# Power_Management.net
KiCad netlist of a schematic drawn in Altium Designer
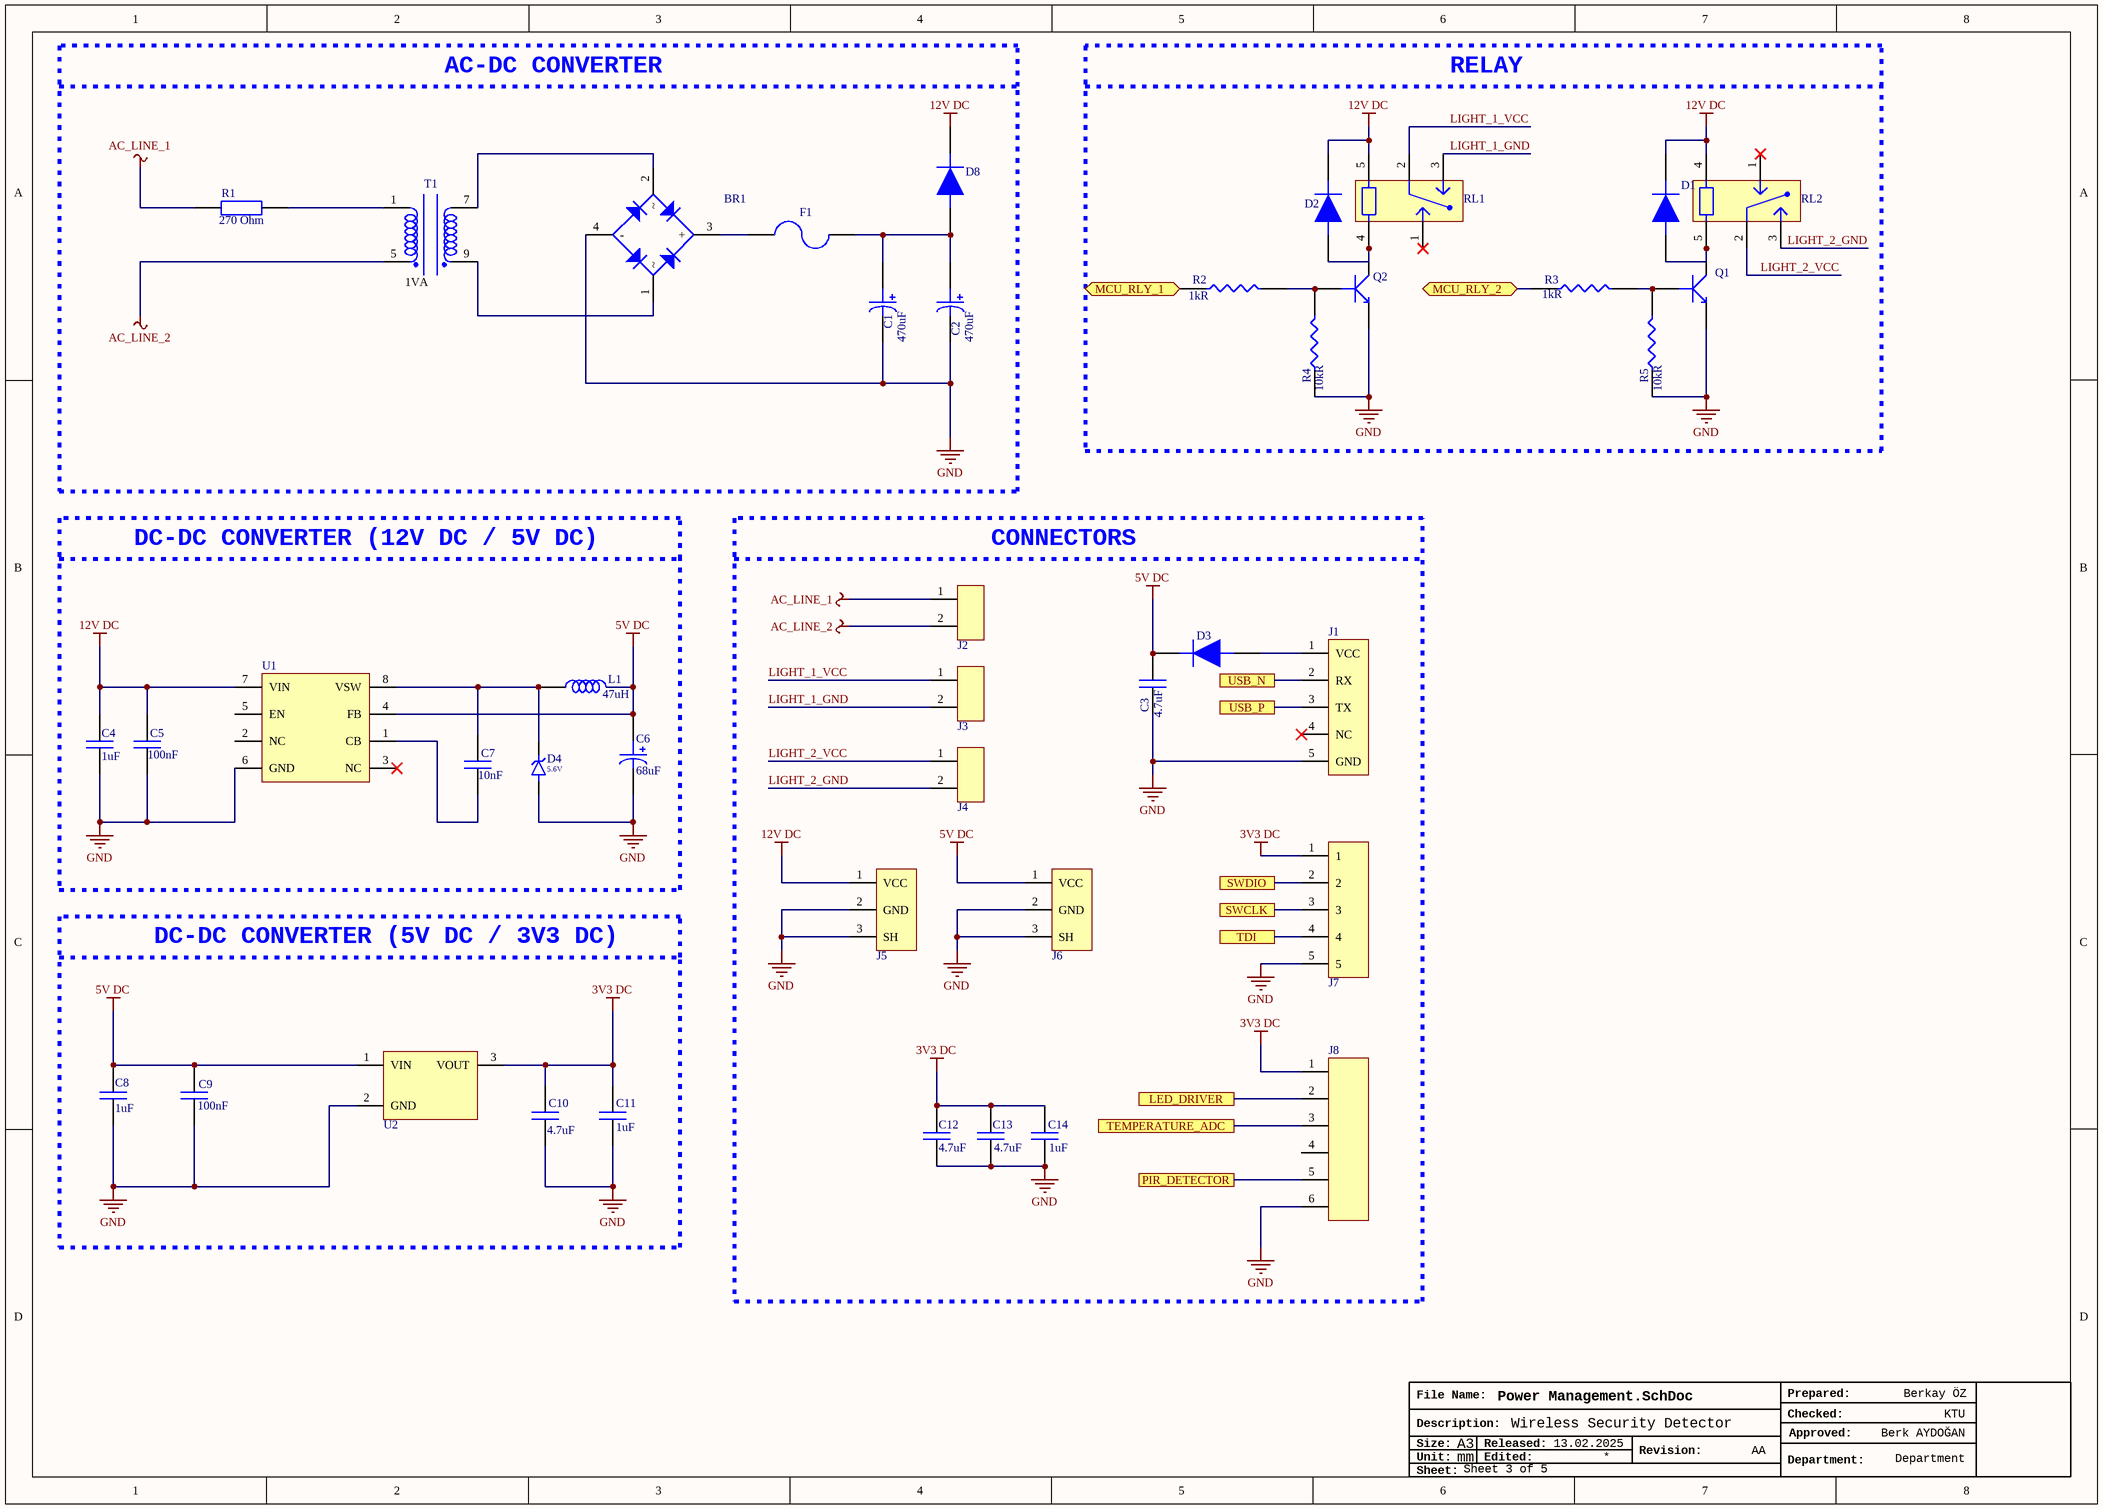
[diagram p0: Power Management.SchDoc]

(export (version "E")
  (design (tool "Eeschema 10.0.6"))
  (components
    (comp (ref "BR1")
      (value "DB105STR")
      (footprint "DB105STR")
      (description "Bridge Rect 1PHASE 600V 1A Db-s")
      (fields
        (field (name "MANUFACTURER") "Sangdest Microelectronics")
        (field (name "MANUFACTURER PART NUMBER") "DB105S")
        (field (name "DESIGNED BY") "berkay")
      )
      (libsource (lib "FirstProject_Library") (part "DB105STR"))
    )
    (comp (ref "C1")
      (value "ESH477M050AH4AA")
      (footprint "CAP_RADIAL_D10_P5")
      (description "Electrolytic capacitor, 470 µF, 50 V (DC), ±20 %, radial, pitch 5 mm, Ø 13 mm")
      (fields
        (field (name "MANUFACTURER") "KEMET")
        (field (name "CAPACITANCE") "470uF")
        (field (name "DESIGNED BY") "berkay")
      )
      (libsource (lib "FirstProject_Library") (part "CAP ALU ELEC 470uF 50V"))
    )
    (comp (ref "C2")
      (value "ESH477M050AH4AA")
      (footprint "CAP_RADIAL_D10_P5")
      (description "Electrolytic capacitor, 470 µF, 50 V (DC), ±20 %, radial, pitch 5 mm, Ø 13 mm")
      (fields
        (field (name "MANUFACTURER") "KEMET")
        (field (name "CAPACITANCE") "470uF")
        (field (name "DESIGNED BY") "berkay")
      )
      (libsource (lib "FirstProject_Library") (part "CAP ALU ELEC 470uF 50V"))
    )
    (comp (ref "C3")
      (value "CL21A475KAQNNNE")
      (footprint "CAP_0805")
      (description "Ceramic Capacitor, 4.7 uF, 25 V, ± 10%, X5R, 0805 [2012 Metric]")
      (fields
        (field (name "MANUFACTURER") "Samsung")
        (field (name "TOLERANCE") "10%")
        (field (name "CAPACITANCE") "4.7uF")
        (field (name "DESIGNED BY") "berkay")
      )
      (libsource (lib "FirstProject_Library") (part "CAP CER 4.7uF 0805"))
    )
    (comp (ref "C4")
      (value "CL21B105KBFNNNE")
      (footprint "CAP_0805")
      (description "Ceramic Capacitor, 1 uF, 50 V, ï¿½ 10%, X7R, 0805 [2012 Metric]")
      (fields
        (field (name "MANUFACTURER") "Samsung")
        (field (name "TOLERANCE") "10%")
        (field (name "CAPACITANCE") "1uF")
        (field (name "DESIGNED BY") "berkay")
      )
      (libsource (lib "FirstProject_Library") (part "CAP CER 1uF 0805"))
    )
    (comp (ref "C5")
      (value "C0603C104K4RACTU")
      (footprint "CAP_0603")
      (description "Ceramic Capacitor, 0.1 uF, 16 V, ï¿½ 10%, X7R, 0603 [1608 Metric]")
      (fields
        (field (name "MANUFACTURER") "KEMET")
        (field (name "TOLERANCE") "10%")
        (field (name "CAPACITANCE") "100nF")
        (field (name "DESIGNED BY") "berkay")
      )
      (libsource (lib "FirstProject_Library") (part "CAP CER 100nF 0603"))
    )
    (comp (ref "C6")
      (value "EEV686M035A9HAA")
      (footprint "CAP_EEVSERIES")
      (description "Cap Aluminum Lytic 68uF 35V 20%( 6.3 X 7.7mm) SMD 0.34 Ohm 280mA 2000h 105C T/R")
      (fields
        (field (name "MANUFACTURER") "KEMET")
        (field (name "CAPACITANCE") "68uF")
        (field (name "DESIGNED BY") "berkay")
      )
      (libsource (lib "FirstProject_Library") (part "CAP ALU 68uF"))
    )
    (comp (ref "C7")
      (value "0603B103K160CT")
      (footprint "CAP_0603")
      (description "Ceramic Capacitor, 10 nF, ± 10%, 0603")
      (fields
        (field (name "MANUFACTURER") "Walsin Technologies")
        (field (name "CAPACITANCE") "10nF")
        (field (name "DESIGNED BY") "berkay")
      )
      (libsource (lib "FirstProject_Library") (part "CAP CER 10nF 0603"))
    )
    (comp (ref "C8")
      (value "CL21B105KBFNNNE")
      (footprint "CAP_0805")
      (description "Ceramic Capacitor, 1 uF, 50 V, ï¿½ 10%, X7R, 0805 [2012 Metric]")
      (fields
        (field (name "MANUFACTURER") "Samsung")
        (field (name "TOLERANCE") "10%")
        (field (name "CAPACITANCE") "1uF")
        (field (name "DESIGNED BY") "berkay")
      )
      (libsource (lib "FirstProject_Library") (part "CAP CER 1uF 0805"))
    )
    (comp (ref "C9")
      (value "C0603C104K4RACTU")
      (footprint "CAP_0603")
      (description "Ceramic Capacitor, 0.1 uF, 16 V, ï¿½ 10%, X7R, 0603 [1608 Metric]")
      (fields
        (field (name "MANUFACTURER") "KEMET")
        (field (name "TOLERANCE") "10%")
        (field (name "CAPACITANCE") "100nF")
        (field (name "DESIGNED BY") "berkay")
      )
      (libsource (lib "FirstProject_Library") (part "CAP CER 100nF 0603"))
    )
    (comp (ref "C10")
      (value "CL21A475KAQNNNE")
      (footprint "CAP_0805")
      (description "Ceramic Capacitor, 4.7 uF, 25 V, ± 10%, X5R, 0805 [2012 Metric]")
      (fields
        (field (name "MANUFACTURER") "Samsung")
        (field (name "TOLERANCE") "10%")
        (field (name "CAPACITANCE") "4.7uF")
        (field (name "DESIGNED BY") "berkay")
      )
      (libsource (lib "FirstProject_Library") (part "CAP CER 4.7uF 0805"))
    )
    (comp (ref "C11")
      (value "CL21B105KBFNNNE")
      (footprint "CAP_0805")
      (description "Ceramic Capacitor, 1 uF, 50 V, ï¿½ 10%, X7R, 0805 [2012 Metric]")
      (fields
        (field (name "MANUFACTURER") "Samsung")
        (field (name "TOLERANCE") "10%")
        (field (name "CAPACITANCE") "1uF")
        (field (name "DESIGNED BY") "berkay")
      )
      (libsource (lib "FirstProject_Library") (part "CAP CER 1uF 0805"))
    )
    (comp (ref "C12")
      (value "CL21A475KAQNNNE")
      (footprint "CAP_0805")
      (description "Ceramic Capacitor, 4.7 uF, 25 V, ± 10%, X5R, 0805 [2012 Metric]")
      (fields
        (field (name "MANUFACTURER") "Samsung")
        (field (name "TOLERANCE") "10%")
        (field (name "CAPACITANCE") "4.7uF")
        (field (name "DESIGNED BY") "berkay")
      )
      (libsource (lib "FirstProject_Library") (part "CAP CER 4.7uF 0805"))
    )
    (comp (ref "C13")
      (value "CL21A475KAQNNNE")
      (footprint "CAP_0805")
      (description "Ceramic Capacitor, 4.7 uF, 25 V, ± 10%, X5R, 0805 [2012 Metric]")
      (fields
        (field (name "MANUFACTURER") "Samsung")
        (field (name "TOLERANCE") "10%")
        (field (name "CAPACITANCE") "4.7uF")
        (field (name "DESIGNED BY") "berkay")
      )
      (libsource (lib "FirstProject_Library") (part "CAP CER 4.7uF 0805"))
    )
    (comp (ref "C14")
      (value "CL21B105KBFNNNE")
      (footprint "CAP_0805")
      (description "Ceramic Capacitor, 1 uF, 50 V, ï¿½ 10%, X7R, 0805 [2012 Metric]")
      (fields
        (field (name "MANUFACTURER") "Samsung")
        (field (name "TOLERANCE") "10%")
        (field (name "CAPACITANCE") "1uF")
        (field (name "DESIGNED BY") "berkay")
      )
      (libsource (lib "FirstProject_Library") (part "CAP CER 1uF 0805"))
    )
    (comp (ref "D1")
      (value "1N4148WS")
      (footprint "SOD323F")
      (description "Diode Ultra Fast Recovery Rectifier 75V 0.15A 2-Pin SOD-323F T/R")
      (fields
        (field (name "MANUFACTURER") "ON Semiconductor / Fairchild")
        (field (name "DESIGNED BY") "berkay")
      )
      (libsource (lib "FirstProject_Library") (part "1N4148WS"))
    )
    (comp (ref "D2")
      (value "1N4148WS")
      (footprint "SOD323F")
      (description "Diode Ultra Fast Recovery Rectifier 75V 0.15A 2-Pin SOD-323F T/R")
      (fields
        (field (name "MANUFACTURER") "ON Semiconductor / Fairchild")
        (field (name "DESIGNED BY") "berkay")
      )
      (libsource (lib "FirstProject_Library") (part "1N4148WS"))
    )
    (comp (ref "D3")
      (value "1N4148WS")
      (footprint "SOD323F")
      (description "Diode Ultra Fast Recovery Rectifier 75V 0.15A 2-Pin SOD-323F T/R")
      (fields
        (field (name "MANUFACTURER") "ON Semiconductor / Fairchild")
        (field (name "DESIGNED BY") "berkay")
      )
      (libsource (lib "FirstProject_Library") (part "1N4148WS"))
    )
    (comp (ref "D4")
      (value "1SMB5919BT3G")
      (footprint "SMB")
      (description "Zener Diode 5.6 V 3 W ±5% Surface Mount SMB")
      (fields
        (field (name "MANUFACTURER") "ON Semiconductor")
        (field (name "VOLTAGE RATING (DC)") "5.6V")
        (field (name "DESIGNED BY") "berkay")
      )
      (libsource (lib "FirstProject_Library") (part "1SMB5919BT3G"))
    )
    (comp (ref "D8")
      (value "1N4148WS")
      (footprint "SOD323F")
      (description "Diode Ultra Fast Recovery Rectifier 75V 0.15A 2-Pin SOD-323F T/R")
      (fields
        (field (name "MANUFACTURER") "ON Semiconductor / Fairchild")
        (field (name "DESIGNED BY") "berkay")
      )
      (libsource (lib "FirstProject_Library") (part "1N4148WS"))
    )
    (comp (ref "F1")
      (value "3413.0216.22")
      (footprint "3413.0216.22")
      (description "Fuse Chip Fast Acting 1A 32V SMD Solder Pad 1206 Glass T/R VDE/cULus")
      (fields (field (name "MANUFACTURER") "Schurter") (field (name "DESIGNED BY") "berkay"))
      (libsource (lib "FirstProject_Library") (part "FUSE 3413.0216.22"))
    )
    (comp (ref "J1")
      (value "10118192-0001LF")
      (footprint "MICRO_B_USB")
      (description "CONN USB MICRO B RECPT SMT R/A\r\n(Designator'e USB?'de denebilirdi)")
      (fields (field (name "MANUFACTURER") "Amphenol ICC / FCI") (field (name "DESIGNED BY") "berkay"))
      (libsource (lib "FirstProject_Library") (part "Micro B USB Connector"))
    )
    (comp (ref "J2")
      (value "TBP01R1-508-02BE")
      (footprint "TBP01R1-508")
      (description "2~24 Poles, Pluggable, Receptacle, Horizontal, 5.08 Pitch, Terminal Block Connector")
      (fields (field (name "MANUFACTURER") "CUI Devices") (field (name "DESIGNED BY") "berkay"))
      (libsource (lib "FirstProject_Library") (part "TBP01R1-508-02BE"))
    )
    (comp (ref "J3")
      (value "TBP01R1-508-02BE")
      (footprint "TBP01R1-508")
      (description "2~24 Poles, Pluggable, Receptacle, Horizontal, 5.08 Pitch, Terminal Block Connector")
      (fields (field (name "MANUFACTURER") "CUI Devices") (field (name "DESIGNED BY") "berkay"))
      (libsource (lib "FirstProject_Library") (part "TBP01R1-508-02BE"))
    )
    (comp (ref "J4")
      (value "TBP01R1-508-02BE")
      (footprint "TBP01R1-508")
      (description "2~24 Poles, Pluggable, Receptacle, Horizontal, 5.08 Pitch, Terminal Block Connector")
      (fields (field (name "MANUFACTURER") "CUI Devices") (field (name "DESIGNED BY") "berkay"))
      (libsource (lib "FirstProject_Library") (part "TBP01R1-508-02BE"))
    )
    (comp (ref "J5")
      (value "PJ-037AH-SMT-TR")
      (footprint "JACK")
      (description "2.0 x 6.3 mm, 5.0 A, Horizontal, Surface Mount (SMT), Dc Power Jack Connector")
      (fields (field (name "MANUFACTURER") "CUI") (field (name "DESIGNED BY") "berkay"))
      (libsource (lib "FirstProject_Library") (part "PJ-037AH-SMT-TR"))
    )
    (comp (ref "J6")
      (value "PJ-037AH-SMT-TR")
      (footprint "JACK")
      (description "2.0 x 6.3 mm, 5.0 A, Horizontal, Surface Mount (SMT), Dc Power Jack Connector")
      (fields (field (name "MANUFACTURER") "CUI") (field (name "DESIGNED BY") "berkay"))
      (libsource (lib "FirstProject_Library") (part "PJ-037AH-SMT-TR"))
    )
    (comp (ref "J7")
      (value "SMH-105-02-L-S")
      (footprint "PIN_HEADER_1X5_RA")
      (description "PCB Receptacle, Board-to-Board, 2.54 mm, 1 Rows, 5 Contacts, Surface Mount, SMH")
      (fields (field (name "MANUFACTURER") "Samtec") (field (name "DESIGNED BY") "berkay"))
      (libsource (lib "FirstProject_Library") (part "SMH-105-02-L-S"))
    )
    (comp (ref "J8")
      (value "64800611622")
      (footprint "64800611622")
      (description "WR-WTB Wire-to-Board Connectors 1.50 mm")
      (fields (field (name "MANUFACTURER") "Wurth Electronics"))
      (libsource (lib "FirstProject_Library") (part "64800611622_conn_6pin"))
    )
    (comp (ref "L1")
      (value "78438335470")
      (footprint "IND_1212")
      (description "Power Inductor, Aec-Q200, 47Uh, 0.39A Rohs Compliant: Yes ¦Wurth Elektronik 78438335470")
      (fields
        (field (name "MANUFACTURER") "Wurth Electronics")
        (field (name "TOLERANCE") "30%")
        (field (name "INDUCTANCE") "47uH")
        (field (name "DESIGNED BY") "berkay")
      )
      (libsource (lib "FirstProject_Library") (part "IND 47uH"))
    )
    (comp (ref "Q1")
      (value "MMBT3904-7-F")
      (footprint "SOT23F")
      (description "Transistor General Purpose BJT NPN 40 Volt 0.2A Automotive 3-Pin SOT-23")
      (fields (field (name "MANUFACTURER") "Diodes Zetex") (field (name "DESIGNED BY") "berkay"))
      (libsource (lib "FirstProject_Library") (part "MMBT3904-7-F"))
    )
    (comp (ref "Q2")
      (value "MMBT3904-7-F")
      (footprint "SOT23F")
      (description "Transistor General Purpose BJT NPN 40 Volt 0.2A Automotive 3-Pin SOT-23")
      (fields (field (name "MANUFACTURER") "Diodes Zetex") (field (name "DESIGNED BY") "berkay"))
      (libsource (lib "FirstProject_Library") (part "MMBT3904-7-F"))
    )
    (comp (ref "R1")
      (value "5WD27")
      (footprint "RES_AXIAL_W")
      (description "270 OHM RESISTOR")
      (fields
        (field (name "TOLERANCE") "5%")
        (field (name "RESISTANCE VALUE") "270 Ohm")
        (field (name "DESIGNED BY") "berkay")
      )
      (libsource (lib "FirstProject_Library") (part "5WD27"))
    )
    (comp (ref "R2")
      (value "RC0603FR-071KL")
      (footprint "RES_0603")
      (description "SMD Chip Resistor, 1 kOhm, ï¿½ 1%, 100 mW, 0603 [1608 Metric], Thick Film, General Purpose")
      (fields
        (field (name "MANUFACTURER") "Yageo")
        (field (name "TOLERANCE") "1%")
        (field (name "RESISTANCE") "1kR")
        (field (name "DESIGNED BY") "berkay")
      )
      (libsource (lib "FirstProject_Library") (part "RES 1K OHM 0603"))
    )
    (comp (ref "R3")
      (value "RC0603FR-071KL")
      (footprint "RES_0603")
      (description "SMD Chip Resistor, 1 kOhm, ï¿½ 1%, 100 mW, 0603 [1608 Metric], Thick Film, General Purpose")
      (fields
        (field (name "MANUFACTURER") "Yageo")
        (field (name "TOLERANCE") "1%")
        (field (name "RESISTANCE") "1kR")
        (field (name "DESIGNED BY") "berkay")
      )
      (libsource (lib "FirstProject_Library") (part "RES 1K OHM 0603"))
    )
    (comp (ref "R4")
      (value "RC0603FR-0710KL")
      (footprint "RES_0603")
      (description "SMD Chip Resistor, 10 kOhm, ï¿½ 1%, 100 mW, 0603 [1608 Metric], Thick Film, General Purpose")
      (fields
        (field (name "MANUFACTURER") "Yageo")
        (field (name "TOLERANCE") "1%")
        (field (name "RESISTANCE") "10kR")
        (field (name "DESIGNED BY") "berkay")
      )
      (libsource (lib "FirstProject_Library") (part "RES 10K OHM 0603"))
    )
    (comp (ref "R5")
      (value "RC0603FR-0710KL")
      (footprint "RES_0603")
      (description "SMD Chip Resistor, 10 kOhm, ï¿½ 1%, 100 mW, 0603 [1608 Metric], Thick Film, General Purpose")
      (fields
        (field (name "MANUFACTURER") "Yageo")
        (field (name "TOLERANCE") "1%")
        (field (name "RESISTANCE") "10kR")
        (field (name "DESIGNED BY") "berkay")
      )
      (libsource (lib "FirstProject_Library") (part "RES 10K OHM 0603"))
    )
    (comp (ref "RL1")
      (value "ALQ112")
      (footprint "ALQ112")
      (description "Electromechanical Relay 12VDC 360Ohm 10(NO)/3(NC)A SPDT (( 20mm 10mm 16mm)) THT Power Relay")
      (fields (field (name "MANUFACTURER") "Panasonic") (field (name "DESIGNED BY") "berkay"))
      (libsource (lib "FirstProject_Library") (part "ALQ112"))
    )
    (comp (ref "RL2")
      (value "ALQ112")
      (footprint "ALQ112")
      (description "Electromechanical Relay 12VDC 360Ohm 10(NO)/3(NC)A SPDT (( 20mm 10mm 16mm)) THT Power Relay")
      (fields (field (name "MANUFACTURER") "Panasonic") (field (name "DESIGNED BY") "berkay"))
      (libsource (lib "") (part "ALQ112_1"))
    )
    (comp (ref "T1")
      (value "BV302S12010-ZU")
      (footprint "BV302S")
      (description "230-12 Transformer 1VA")
      (fields
        (field (name "MANUFACTURER") "Zettler Magnetics")
        (field (name "RATED POWER") "1VA")
        (field (name "DESIGNED BY") "berkay")
      )
      (libsource (lib "FirstProject_Library") (part "BV302S12010-ZU"))
    )
    (comp (ref "U1")
      (value "LM2675MX-12/NOPB")
      (footprint "SOIC 8")
      (description "Buck Switching Regulator IC Positive Fixed 12V 1 Output 1A 8-SOIC (0.154\", 3.90mm Width)")
      (fields (field (name "MANUFACTURER") "TI National Semiconductor") (field (name "DESIGNED BY") "berkay"))
      (libsource (lib "FirstProject_Library") (part "LM2675MX-12/NOPB"))
    )
    (comp (ref "U2")
      (value "AP7361-33E-13")
      (footprint "SOT223")
      (description "AP7361 Series 3.3 V 1 A Low SMT Dropout Fixed-Mode Regulator - SOT-223")
      (fields (field (name "MANUFACTURER") "Diodes") (field (name "DESIGNED BY") "berkay"))
      (libsource (lib "FirstProject_Library") (part "AP7361-33E-13"))
    )
  )
  (nets
    (net (code "1") (name "/LED_DRIVER") (class "Default")
      (node (ref "J8") (pin "2") (pinfunction "2_2") (pintype "passive"))
    )
    (net (code "2") (name "/LIGHT_1_GND") (class "Default")
      (node (ref "J3") (pin "2") (pinfunction "2_2") (pintype "passive"))
      (node (ref "RL1") (pin "3") (pinfunction "3_3") (pintype "passive"))
    )
    (net (code "3") (name "/LIGHT_1_VCC") (class "Default")
      (node (ref "J3") (pin "1") (pinfunction "1_1") (pintype "passive"))
      (node (ref "RL1") (pin "2") (pinfunction "2_2") (pintype "passive"))
    )
    (net (code "4") (name "/LIGHT_2_GND") (class "Default")
      (node (ref "J4") (pin "2") (pinfunction "2_2") (pintype "passive"))
      (node (ref "RL2") (pin "3") (pinfunction "3_3") (pintype "passive"))
    )
    (net (code "5") (name "/LIGHT_2_VCC") (class "Default")
      (node (ref "J4") (pin "1") (pinfunction "1_1") (pintype "passive"))
      (node (ref "RL2") (pin "2") (pinfunction "2_2") (pintype "passive"))
    )
    (net (code "6") (name "/MCU_RLY_1") (class "Default")
      (node (ref "R2") (pin "1") (pinfunction "1_1") (pintype "passive"))
    )
    (net (code "7") (name "/MCU_RLY_2") (class "Default")
      (node (ref "R3") (pin "1") (pinfunction "1_1") (pintype "passive"))
    )
    (net (code "8") (name "/PIR_DETECTOR") (class "Default")
      (node (ref "J8") (pin "5") (pinfunction "5_5") (pintype "passive"))
    )
    (net (code "9") (name "/SWCLK") (class "Default")
      (node (ref "J7") (pin "3") (pinfunction "3_3") (pintype "passive"))
    )
    (net (code "10") (name "/SWDIO") (class "Default")
      (node (ref "J7") (pin "2") (pinfunction "2_2") (pintype "passive"))
    )
    (net (code "11") (name "/TDI") (class "Default")
      (node (ref "J7") (pin "4") (pinfunction "4_4") (pintype "passive"))
    )
    (net (code "12") (name "/TEMPERATURE_ADC") (class "Default")
      (node (ref "J8") (pin "3") (pinfunction "3_3") (pintype "passive"))
    )
    (net (code "13") (name "/USB_N") (class "Default")
      (node (ref "J1") (pin "2") (pinfunction "RX_2") (pintype "passive"))
    )
    (net (code "14") (name "/USB_P") (class "Default")
      (node (ref "J1") (pin "3") (pinfunction "TX_3") (pintype "passive"))
    )
    (net (code "15") (name "3V3 DC") (class "Default")
      (node (ref "C10") (pin "2") (pinfunction "2_2") (pintype "passive"))
      (node (ref "C11") (pin "2") (pinfunction "2_2") (pintype "passive"))
      (node (ref "C12") (pin "2") (pinfunction "2_2") (pintype "passive"))
      (node (ref "C13") (pin "2") (pinfunction "2_2") (pintype "passive"))
      (node (ref "C14") (pin "2") (pinfunction "2_2") (pintype "passive"))
      (node (ref "J7") (pin "1") (pinfunction "1_1") (pintype "passive"))
      (node (ref "J8") (pin "1") (pinfunction "1_1") (pintype "passive"))
      (node (ref "U2") (pin "3") (pinfunction "VOUT_3") (pintype "passive"))
    )
    (net (code "16") (name "5V DC") (class "Default")
      (node (ref "C3") (pin "2") (pinfunction "2_2") (pintype "passive"))
      (node (ref "C6") (pin "1") (pinfunction "1_1") (pintype "passive"))
      (node (ref "C8") (pin "2") (pinfunction "2_2") (pintype "passive"))
      (node (ref "C9") (pin "2") (pinfunction "2_2") (pintype "passive"))
      (node (ref "D3") (pin "C") (pinfunction "C_C") (pintype "passive"))
      (node (ref "J6") (pin "1") (pinfunction "VCC_1") (pintype "power_in"))
      (node (ref "L1") (pin "2") (pinfunction "2_2") (pintype "passive"))
      (node (ref "U1") (pin "4") (pinfunction "FB_4") (pintype "passive"))
      (node (ref "U2") (pin "1") (pinfunction "VIN_1") (pintype "passive"))
    )
    (net (code "17") (name "12V DC") (class "Default")
      (node (ref "C4") (pin "2") (pinfunction "2_2") (pintype "passive"))
      (node (ref "C5") (pin "2") (pinfunction "2_2") (pintype "passive"))
      (node (ref "D1") (pin "C") (pinfunction "C_C") (pintype "passive"))
      (node (ref "D2") (pin "C") (pinfunction "C_C") (pintype "passive"))
      (node (ref "D8") (pin "C") (pinfunction "C_C") (pintype "passive"))
      (node (ref "J5") (pin "1") (pinfunction "VCC_1") (pintype "power_in"))
      (node (ref "RL1") (pin "5") (pinfunction "5_5") (pintype "passive"))
      (node (ref "RL2") (pin "4") (pinfunction "4_4") (pintype "passive"))
      (node (ref "U1") (pin "7") (pinfunction "VIN_7") (pintype "passive"))
    )
    (net (code "18") (name "AC_LINE_1") (class "Default")
      (node (ref "J2") (pin "1") (pinfunction "1_1") (pintype "passive"))
      (node (ref "R1") (pin "1") (pinfunction "1_1") (pintype "passive"))
    )
    (net (code "19") (name "AC_LINE_2") (class "Default")
      (node (ref "J2") (pin "2") (pinfunction "2_2") (pintype "passive"))
      (node (ref "T1") (pin "5") (pinfunction "5_5") (pintype "passive"))
    )
    (net (code "20") (name "GND") (class "Default")
      (node (ref "BR1") (pin "4") (pinfunction "-_4") (pintype "passive"))
      (node (ref "C1") (pin "2") (pinfunction "2_2") (pintype "passive"))
      (node (ref "C10") (pin "1") (pinfunction "1_1") (pintype "passive"))
      (node (ref "C11") (pin "1") (pinfunction "1_1") (pintype "passive"))
      (node (ref "C12") (pin "1") (pinfunction "1_1") (pintype "passive"))
      (node (ref "C13") (pin "1") (pinfunction "1_1") (pintype "passive"))
      (node (ref "C14") (pin "1") (pinfunction "1_1") (pintype "passive"))
      (node (ref "C2") (pin "2") (pinfunction "2_2") (pintype "passive"))
      (node (ref "C3") (pin "1") (pinfunction "1_1") (pintype "passive"))
      (node (ref "C4") (pin "1") (pinfunction "1_1") (pintype "passive"))
      (node (ref "C5") (pin "1") (pinfunction "1_1") (pintype "passive"))
      (node (ref "C6") (pin "2") (pinfunction "2_2") (pintype "passive"))
      (node (ref "C8") (pin "1") (pinfunction "1_1") (pintype "passive"))
      (node (ref "C9") (pin "1") (pinfunction "1_1") (pintype "passive"))
      (node (ref "D4") (pin "A") (pinfunction "A_A") (pintype "passive"))
      (node (ref "J1") (pin "5") (pinfunction "GND_5") (pintype "passive"))
      (node (ref "J5") (pin "2") (pinfunction "GND_2") (pintype "power_in"))
      (node (ref "J5") (pin "3") (pinfunction "SH_3") (pintype "power_in"))
      (node (ref "J6") (pin "2") (pinfunction "GND_2") (pintype "power_in"))
      (node (ref "J6") (pin "3") (pinfunction "SH_3") (pintype "power_in"))
      (node (ref "J7") (pin "5") (pinfunction "5_5") (pintype "passive"))
      (node (ref "J8") (pin "6") (pinfunction "6_6") (pintype "passive"))
      (node (ref "Q1") (pin "2") (pinfunction "E_2") (pintype "passive"))
      (node (ref "Q2") (pin "2") (pinfunction "E_2") (pintype "passive"))
      (node (ref "R4") (pin "1") (pinfunction "1_1") (pintype "passive"))
      (node (ref "R5") (pin "1") (pinfunction "1_1") (pintype "passive"))
      (node (ref "U1") (pin "6") (pinfunction "GND_6") (pintype "passive"))
      (node (ref "U2") (pin "2") (pinfunction "GND_2") (pintype "passive"))
    )
    (net (code "21") (name "Net-(BR1-+)") (class "Default")
      (node (ref "BR1") (pin "3") (pinfunction "+_3") (pintype "passive"))
      (node (ref "F1") (pin "2") (pinfunction "2_2") (pintype "passive"))
    )
    (net (code "22") (name "Net-(BR1-~-Pad1)") (class "Default")
      (node (ref "BR1") (pin "1") (pinfunction "~_1") (pintype "passive"))
      (node (ref "T1") (pin "9") (pinfunction "9_9") (pintype "passive"))
    )
    (net (code "23") (name "Net-(BR1-~-Pad2)") (class "Default")
      (node (ref "BR1") (pin "2") (pinfunction "~_2") (pintype "passive"))
      (node (ref "T1") (pin "7") (pinfunction "7_7") (pintype "passive"))
    )
    (net (code "24") (name "Net-(C1-Pad1)") (class "Default")
      (node (ref "C1") (pin "1") (pinfunction "1_1") (pintype "passive"))
      (node (ref "C2") (pin "1") (pinfunction "1_1") (pintype "passive"))
      (node (ref "D8") (pin "A") (pinfunction "A_A") (pintype "passive"))
      (node (ref "F1") (pin "1") (pinfunction "1_1") (pintype "passive"))
    )
    (net (code "25") (name "Net-(J1-VCC)") (class "Default")
      (node (ref "D3") (pin "A") (pinfunction "A_A") (pintype "passive"))
      (node (ref "J1") (pin "1") (pinfunction "VCC_1") (pintype "passive"))
    )
    (net (code "26") (name "Net-(Q1-B)") (class "Default")
      (node (ref "Q1") (pin "1") (pinfunction "B_1") (pintype "passive"))
      (node (ref "R3") (pin "2") (pinfunction "2_2") (pintype "passive"))
      (node (ref "R5") (pin "2") (pinfunction "2_2") (pintype "passive"))
    )
    (net (code "27") (name "Net-(Q1-C)") (class "Default")
      (node (ref "D1") (pin "A") (pinfunction "A_A") (pintype "passive"))
      (node (ref "Q1") (pin "3") (pinfunction "C_3") (pintype "passive"))
      (node (ref "RL2") (pin "5") (pinfunction "5_5") (pintype "passive"))
    )
    (net (code "28") (name "Net-(Q2-B)") (class "Default")
      (node (ref "Q2") (pin "1") (pinfunction "B_1") (pintype "passive"))
      (node (ref "R2") (pin "2") (pinfunction "2_2") (pintype "passive"))
      (node (ref "R4") (pin "2") (pinfunction "2_2") (pintype "passive"))
    )
    (net (code "29") (name "Net-(Q2-C)") (class "Default")
      (node (ref "D2") (pin "A") (pinfunction "A_A") (pintype "passive"))
      (node (ref "Q2") (pin "3") (pinfunction "C_3") (pintype "passive"))
      (node (ref "RL1") (pin "4") (pinfunction "4_4") (pintype "passive"))
    )
    (net (code "30") (name "Net-(R1-Pad2)") (class "Default")
      (node (ref "R1") (pin "2") (pinfunction "2_2") (pintype "passive"))
      (node (ref "T1") (pin "1") (pinfunction "1_1") (pintype "passive"))
    )
    (net (code "31") (name "Net-(U1-CB)") (class "Default")
      (node (ref "C7") (pin "1") (pinfunction "1_1") (pintype "passive"))
      (node (ref "U1") (pin "1") (pinfunction "CB_1") (pintype "passive"))
    )
    (net (code "32") (name "Net-(U1-VSW)") (class "Default")
      (node (ref "C7") (pin "2") (pinfunction "2_2") (pintype "passive"))
      (node (ref "D4") (pin "C") (pinfunction "C_C") (pintype "passive"))
      (node (ref "L1") (pin "1") (pinfunction "1_1") (pintype "passive"))
      (node (ref "U1") (pin "8") (pinfunction "VSW_8") (pintype "passive"))
    )
    (net (code "33") (name "unconnected-(J1-NC-Pad4)") (class "Default")
      (node (ref "J1") (pin "4") (pinfunction "NC_4") (pintype "passive+no_connect"))
    )
    (net (code "34") (name "unconnected-(J8-Pad4)") (class "Default")
      (node (ref "J8") (pin "4") (pinfunction "4_4") (pintype "passive"))
    )
    (net (code "35") (name "unconnected-(RL1-Pad1)") (class "Default")
      (node (ref "RL1") (pin "1") (pinfunction "1_1") (pintype "passive+no_connect"))
    )
    (net (code "36") (name "unconnected-(RL2-Pad1)") (class "Default")
      (node (ref "RL2") (pin "1") (pinfunction "1_1") (pintype "passive+no_connect"))
    )
    (net (code "37") (name "unconnected-(U1-EN-Pad5)") (class "Default")
      (node (ref "U1") (pin "5") (pinfunction "EN_5") (pintype "passive"))
    )
    (net (code "38") (name "unconnected-(U1-NC-Pad2)") (class "Default")
      (node (ref "U1") (pin "2") (pinfunction "NC_2") (pintype "passive"))
    )
    (net (code "39") (name "unconnected-(U1-NC-Pad3)") (class "Default")
      (node (ref "U1") (pin "3") (pinfunction "NC_3") (pintype "passive+no_connect"))
    )
  )
)
